# Power_Supply.net
KiCad netlist of a schematic drawn in Altium Designer
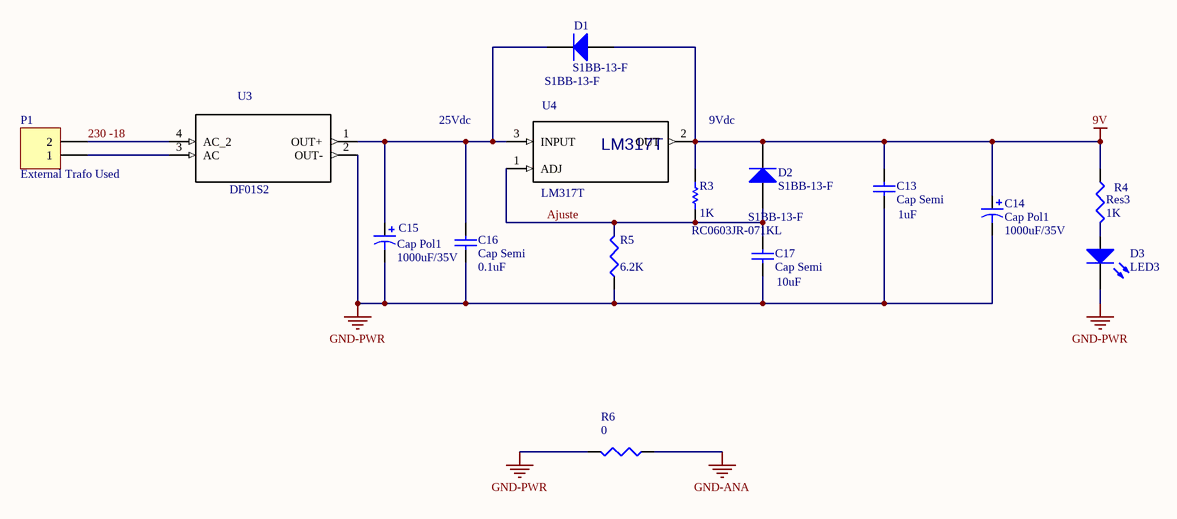
[diagram p0: Power_Supply.SchDoc]

(export (version "E")
  (design (tool "Eeschema 10.0.6"))
  (components
    (comp (ref "C13")
      (value "Cap Semi")
      (footprint "1608[0603]")
      (description "Capacitor (Semiconductor SIM Model) C1608JB1V105K080AB")
      (fields (field (name "ALTIUM_VALUE") "1uF") (field (name "PUBLISHER") "Altium Limited"))
      (libsource (lib "Miscellaneous Devices") (part "Cap Semi"))
    )
    (comp (ref "C14")
      (value "Cap Pol1")
      (footprint "RB7.6-15")
      (description "Polarized Capacitor (Radial) URS1V102MHD")
      (fields (field (name "ALTIUM_VALUE") "1000uF/35V") (field (name "PUBLISHER") "Altium Limited"))
      (libsource (lib "Miscellaneous Devices") (part "Cap Pol1"))
    )
    (comp (ref "C15")
      (value "Cap Pol1")
      (footprint "RB7.6-15")
      (description "Polarized Capacitor (Radial) URS1V102MHD")
      (fields (field (name "ALTIUM_VALUE") "1000uF/35V") (field (name "PUBLISHER") "Altium Limited"))
      (libsource (lib "Miscellaneous Devices") (part "Cap Pol1"))
    )
    (comp (ref "C16")
      (value "Cap Semi")
      (footprint "1608[0603]")
      (description "Capacitor (Semiconductor SIM Model) C0603T104J5RACTU")
      (fields (field (name "ALTIUM_VALUE") "0.1uF") (field (name "PUBLISHER") "Altium Limited"))
      (libsource (lib "Miscellaneous Devices") (part "Cap Semi"))
    )
    (comp (ref "C17")
      (value "Cap Semi")
      (footprint "1608[0603]")
      (description "Capacitor (Semiconductor SIM Model) GRM188R6YA106MA73D")
      (fields (field (name "ALTIUM_VALUE") "10uF") (field (name "PUBLISHER") "Altium Limited"))
      (libsource (lib "Miscellaneous Devices") (part "Cap Semi"))
    )
    (comp (ref "D1")
      (value "S1BB-13-F")
      (footprint "DIOM505270X240")
      (description "100V 1 Amp General Purpose Rectifier")
      (fields (field (name "PN") "S1BB-13-F") (field (name "PUBLISHER") "Altium Limited"))
      (libsource (lib "Miscellaneous Devices") (part "Diode 1N4002"))
    )
    (comp (ref "D2")
      (value "S1BB-13-F")
      (footprint "DIOM505270X240")
      (description "100V 1 Amp General Purpose Rectifier")
      (fields (field (name "PN") "S1BB-13-F") (field (name "PUBLISHER") "Altium Limited"))
      (libsource (lib "Miscellaneous Devices") (part "Diode 1N4002"))
    )
    (comp (ref "D3")
      (value "LED3")
      (footprint "6-0805_L")
      (description "Typical BLUE SiC LED IN-S85ATR")
      (fields (field (name "PUBLISHER") "Altium Limited"))
      (libsource (lib "Miscellaneous Devices") (part "LED3"))
    )
    (comp (ref "P1")
      (value "External Trafo Used")
      (footprint "PCBComponent_1")
      (description "Header, 2-Pin")
      (fields (field (name "PUBLISHER") "Altium Limited"))
      (libsource (lib "Miscellaneous Connectors") (part "MHDR1X2"))
    )
    (comp (ref "R3")
      (value "1K")
      (footprint "J1-0603")
      (description "Resistor ERJ-PA3J102V")
      (fields
        (field (name "PN") "RC0603JR-071KL")
        (field (name "Comment") "Res1")
        (field (name "PUBLISHER") "Altium Limited")
      )
      (libsource (lib "Miscellaneous Devices") (part "Res1"))
    )
    (comp (ref "R4")
      (value "Res3")
      (footprint "J1-0603")
      (description "Resistor ERJ-PA3J102V")
      (fields (field (name "ALTIUM_VALUE") "1K") (field (name "PUBLISHER") "Altium Limited"))
      (libsource (lib "Miscellaneous Devices") (part "Res3"))
    )
    (comp (ref "R5")
      (value "6.2K")
      (footprint "J1-0603")
      (description "Resistor ERJ-PA3J622V")
      (fields (field (name "Comment") "Res3") (field (name "PUBLISHER") "Altium Limited"))
      (libsource (lib "Miscellaneous Devices") (part "Res3"))
    )
    (comp (ref "R6")
      (value "0")
      (footprint "6-0805_N")
      (description "Resistor")
      (fields (field (name "Comment") "Res3") (field (name "PUBLISHER") "Altium Limited"))
      (libsource (lib "Miscellaneous Devices") (part "Res3"))
    )
    (comp (ref "U3")
      (value "DF01S2")
      (footprint "SOT508P985X260-4N")
      (description "DF01S Series 1.5 A 100 V 5 uA Surface Mount Bridge Rectifier -SDIP-4")
      (fields (field (name "MF") "ON Semiconductor") (field (name "DIGI-KEY_PART_NUMBER") "DF01SDI-ND"))
      (libsource (lib "DF01S") (part "DF01S"))
    )
    (comp (ref "U4")
      (value "LM317T")
      (footprint "TO254P460X1020X1945-3P")
      (fields (field (name "MF") "Texas Instruments") (field (name "PN") "LM317T"))
      (libsource (lib "LM317T") (part "LM317T"))
    )
  )
  (nets
    (net (code "1") (name "/230 -18") (class "Default")
      (node (ref "P1") (pin "2") (pinfunction "2_2") (pintype "passive"))
      (node (ref "U3") (pin "4") (pinfunction "AC_2_4") (pintype "input"))
    )
    (net (code "2") (name "/Ajuste") (class "Default")
      (node (ref "C17") (pin "2") (pinfunction "2_2") (pintype "passive"))
      (node (ref "D2") (pin "1") (pinfunction "A_1") (pintype "passive"))
      (node (ref "R3") (pin "2") (pinfunction "2_2") (pintype "passive"))
      (node (ref "R5") (pin "2") (pinfunction "2_2") (pintype "passive"))
      (node (ref "U4") (pin "1") (pinfunction "ADJ_1") (pintype "input"))
    )
    (net (code "3") (name "9V") (class "Default")
      (node (ref "C13") (pin "2") (pinfunction "2_2") (pintype "passive"))
      (node (ref "C14") (pin "1") (pinfunction "1_1") (pintype "passive"))
      (node (ref "D1") (pin "1") (pinfunction "A_1") (pintype "passive"))
      (node (ref "D2") (pin "2") (pinfunction "K_2") (pintype "passive"))
      (node (ref "R3") (pin "1") (pinfunction "1_1") (pintype "passive"))
      (node (ref "R4") (pin "1") (pinfunction "1_1") (pintype "passive"))
      (node (ref "U4") (pin "2") (pinfunction "OUT_2") (pintype "output"))
    )
    (net (code "4") (name "GND-ANA") (class "Default")
      (node (ref "R6") (pin "1") (pinfunction "1_1") (pintype "passive"))
    )
    (net (code "5") (name "GND-PWR") (class "Default")
      (node (ref "C13") (pin "1") (pinfunction "1_1") (pintype "passive"))
      (node (ref "C14") (pin "2") (pinfunction "2_2") (pintype "passive"))
      (node (ref "C15") (pin "2") (pinfunction "2_2") (pintype "passive"))
      (node (ref "C16") (pin "1") (pinfunction "1_1") (pintype "passive"))
      (node (ref "C17") (pin "1") (pinfunction "1_1") (pintype "passive"))
      (node (ref "D3") (pin "2") (pinfunction "K_2") (pintype "passive"))
      (node (ref "R5") (pin "1") (pinfunction "1_1") (pintype "passive"))
      (node (ref "R6") (pin "2") (pinfunction "2_2") (pintype "passive"))
      (node (ref "U3") (pin "2") (pinfunction "OUT-_2") (pintype "output"))
    )
    (net (code "6") (name "Net-(D1-K)") (class "Default")
      (node (ref "C15") (pin "1") (pinfunction "1_1") (pintype "passive"))
      (node (ref "C16") (pin "2") (pinfunction "2_2") (pintype "passive"))
      (node (ref "D1") (pin "2") (pinfunction "K_2") (pintype "passive"))
      (node (ref "U3") (pin "1") (pinfunction "OUT+_1") (pintype "output"))
      (node (ref "U4") (pin "3") (pinfunction "INPUT_3") (pintype "input"))
    )
    (net (code "7") (name "Net-(D3-A)") (class "Default")
      (node (ref "D3") (pin "1") (pinfunction "A_1") (pintype "passive"))
      (node (ref "R4") (pin "2") (pinfunction "2_2") (pintype "passive"))
    )
    (net (code "8") (name "Net-(U3-AC)") (class "Default")
      (node (ref "P1") (pin "1") (pinfunction "1_1") (pintype "passive"))
      (node (ref "U3") (pin "3") (pinfunction "AC_3") (pintype "input"))
    )
  )
)
